# lamp.net
KiCad netlist of a schematic drawn in EAGLE
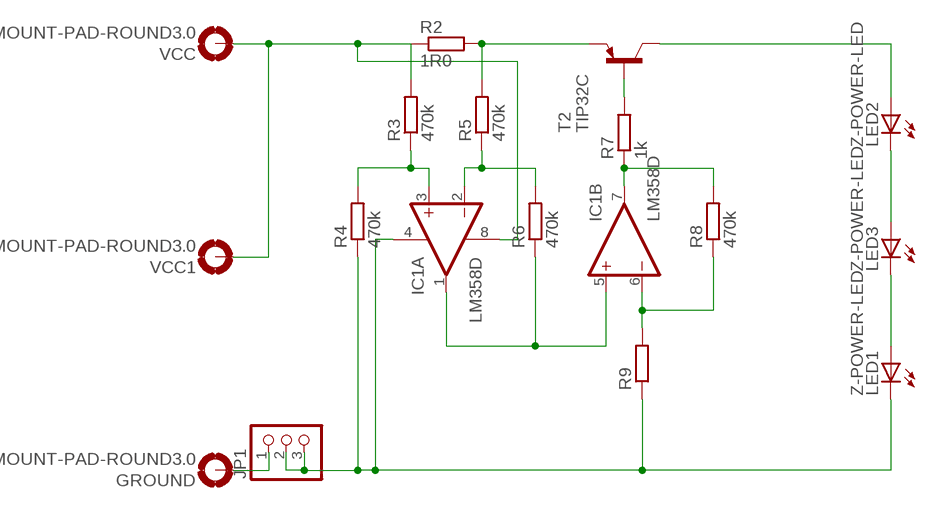
[diagram p0: schematic, sheet 1]

(export (version "E")
  (design (tool "Eeschema 10.0.6"))
  (components
    (comp (ref "GROUND")
      (value "MOUNT-PAD-ROUND3.0")
      (footprint "eagle-import:3,0-PAD")
      (libsource (lib "eagle-import") (part "MOUNT-PAD-ROUND3.0"))
    )
    (comp (ref "IC1")
      (value "LM358D")
      (footprint "eagle-import:SO08")
      (libsource (lib "eagle-import") (part "LM358D"))
    )
    (comp (ref "JP1")
      (value "PINHD-1X3")
      (footprint "eagle-import:1X03")
      (libsource (lib "eagle-import") (part "PINHD-1X3"))
    )
    (comp (ref "LED1")
      (value "Z-POWER-LED")
      (footprint "eagle-import:Z-POWER-LED-PCB-TYPE")
      (libsource (lib "eagle-import") (part "Z-POWER-LED"))
    )
    (comp (ref "LED2")
      (value "Z-POWER-LED")
      (footprint "eagle-import:Z-POWER-LED-PCB-TYPE")
      (libsource (lib "eagle-import") (part "Z-POWER-LED"))
    )
    (comp (ref "LED3")
      (value "Z-POWER-LED")
      (footprint "eagle-import:Z-POWER-LED-PCB-TYPE")
      (libsource (lib "eagle-import") (part "Z-POWER-LED"))
    )
    (comp (ref "R2")
      (value "1R0")
      (footprint "eagle-import:R1210")
      (libsource (lib "eagle-import") (part "R-EU_R1210"))
    )
    (comp (ref "R3")
      (value "470k")
      (footprint "eagle-import:R1206")
      (libsource (lib "eagle-import") (part "R-EU_R1206"))
    )
    (comp (ref "R4")
      (value "470k")
      (footprint "eagle-import:R1206")
      (libsource (lib "eagle-import") (part "R-EU_R1206"))
    )
    (comp (ref "R5")
      (value "470k")
      (footprint "eagle-import:R1206")
      (libsource (lib "eagle-import") (part "R-EU_R1206"))
    )
    (comp (ref "R6")
      (value "470k")
      (footprint "eagle-import:R1206")
      (libsource (lib "eagle-import") (part "R-EU_R1206"))
    )
    (comp (ref "R7")
      (value "1k")
      (footprint "eagle-import:R1206")
      (libsource (lib "eagle-import") (part "R-EU_R1206"))
    )
    (comp (ref "R8")
      (value "470k")
      (footprint "eagle-import:R1206")
      (libsource (lib "eagle-import") (part "R-EU_R1206"))
    )
    (comp (ref "R9")
      (value "R-EU_R1206")
      (footprint "eagle-import:R1206")
      (libsource (lib "eagle-import") (part "R-EU_R1206"))
    )
    (comp (ref "T2")
      (value "TIP32C")
      (footprint "eagle-import:TO220")
      (libsource (lib "eagle-import") (part "TIP32C"))
    )
    (comp (ref "VCC")
      (value "MOUNT-PAD-ROUND3.0")
      (footprint "eagle-import:3,0-PAD")
      (libsource (lib "eagle-import") (part "MOUNT-PAD-ROUND3.0"))
    )
    (comp (ref "VCC1")
      (value "MOUNT-PAD-ROUND3.0")
      (footprint "eagle-import:3,0-PAD")
      (libsource (lib "eagle-import") (part "MOUNT-PAD-ROUND3.0"))
    )
  )
  (nets
    (net (code "1") (name "Net-(GROUND-MOUNT)") (class "Default")
      (node (ref "GROUND") (pin "B3,0") (pinfunction "MOUNT_B3,0") (pintype "passive"))
      (node (ref "JP1") (pin "1") (pinfunction "1_1") (pintype "passive"))
    )
    (net (code "2") (name "Net-(IC1A-+IN)") (class "Default")
      (node (ref "IC1") (pin "3") (pinfunction "+IN_3") (pintype "input"))
      (node (ref "R3") (pin "1") (pinfunction "1_1") (pintype "passive"))
      (node (ref "R4") (pin "2") (pinfunction "2_2") (pintype "passive"))
    )
    (net (code "3") (name "Net-(IC1A--IN)") (class "Default")
      (node (ref "IC1") (pin "2") (pinfunction "-IN_2") (pintype "input"))
      (node (ref "R5") (pin "1") (pinfunction "1_1") (pintype "passive"))
      (node (ref "R6") (pin "2") (pinfunction "2_2") (pintype "passive"))
    )
    (net (code "4") (name "Net-(IC1A-OUT)") (class "Default")
      (node (ref "IC1") (pin "1") (pinfunction "OUT_1") (pintype "output"))
      (node (ref "IC1") (pin "5") (pinfunction "+IN_5") (pintype "input"))
      (node (ref "R6") (pin "1") (pinfunction "1_1") (pintype "passive"))
    )
    (net (code "5") (name "Net-(IC1B--IN)") (class "Default")
      (node (ref "IC1") (pin "6") (pinfunction "-IN_6") (pintype "input"))
      (node (ref "R8") (pin "1") (pinfunction "1_1") (pintype "passive"))
      (node (ref "R9") (pin "2") (pinfunction "2_2") (pintype "passive"))
    )
    (net (code "6") (name "Net-(IC1B-OUT)") (class "Default")
      (node (ref "IC1") (pin "7") (pinfunction "OUT_7") (pintype "output"))
      (node (ref "R7") (pin "1") (pinfunction "1_1") (pintype "passive"))
      (node (ref "R8") (pin "2") (pinfunction "2_2") (pintype "passive"))
    )
    (net (code "7") (name "Net-(IC1C-V+)") (class "Default")
      (node (ref "IC1") (pin "8") (pinfunction "V+_8") (pintype "power_in"))
      (node (ref "R2") (pin "1") (pinfunction "1_1") (pintype "passive"))
      (node (ref "R3") (pin "2") (pinfunction "2_2") (pintype "passive"))
      (node (ref "VCC") (pin "B3,0") (pinfunction "MOUNT_B3,0") (pintype "passive"))
      (node (ref "VCC1") (pin "B3,0") (pinfunction "MOUNT_B3,0") (pintype "passive"))
    )
    (net (code "8") (name "Net-(IC1C-V-)") (class "Default")
      (node (ref "IC1") (pin "4") (pinfunction "V-_4") (pintype "power_in"))
      (node (ref "JP1") (pin "2") (pinfunction "2_2") (pintype "passive"))
      (node (ref "JP1") (pin "3") (pinfunction "3_3") (pintype "passive"))
      (node (ref "LED1") (pin "C") (pinfunction "C_C") (pintype "passive"))
      (node (ref "R4") (pin "1") (pinfunction "1_1") (pintype "passive"))
      (node (ref "R9") (pin "1") (pinfunction "1_1") (pintype "passive"))
    )
    (net (code "9") (name "Net-(LED1-PadA)") (class "Default")
      (node (ref "LED1") (pin "A") (pinfunction "A_A") (pintype "passive"))
      (node (ref "LED3") (pin "C") (pinfunction "C_C") (pintype "passive"))
    )
    (net (code "10") (name "Net-(LED2-PadC)") (class "Default")
      (node (ref "LED2") (pin "C") (pinfunction "C_C") (pintype "passive"))
      (node (ref "LED3") (pin "A") (pinfunction "A_A") (pintype "passive"))
    )
    (net (code "11") (name "Net-(T2-B)") (class "Default")
      (node (ref "R7") (pin "2") (pinfunction "2_2") (pintype "passive"))
      (node (ref "T2") (pin "1") (pinfunction "B_1") (pintype "passive"))
    )
    (net (code "12") (name "Net-(T2-C)") (class "Default")
      (node (ref "LED2") (pin "A") (pinfunction "A_A") (pintype "passive"))
      (node (ref "T2") (pin "2") (pinfunction "C_2") (pintype "passive"))
    )
    (net (code "13") (name "Net-(T2-E)") (class "Default")
      (node (ref "R2") (pin "2") (pinfunction "2_2") (pintype "passive"))
      (node (ref "R5") (pin "2") (pinfunction "2_2") (pintype "passive"))
      (node (ref "T2") (pin "3") (pinfunction "E_3") (pintype "passive"))
    )
  )
)
